# seletor.net
KiCad netlist of a schematic drawn in EAGLE
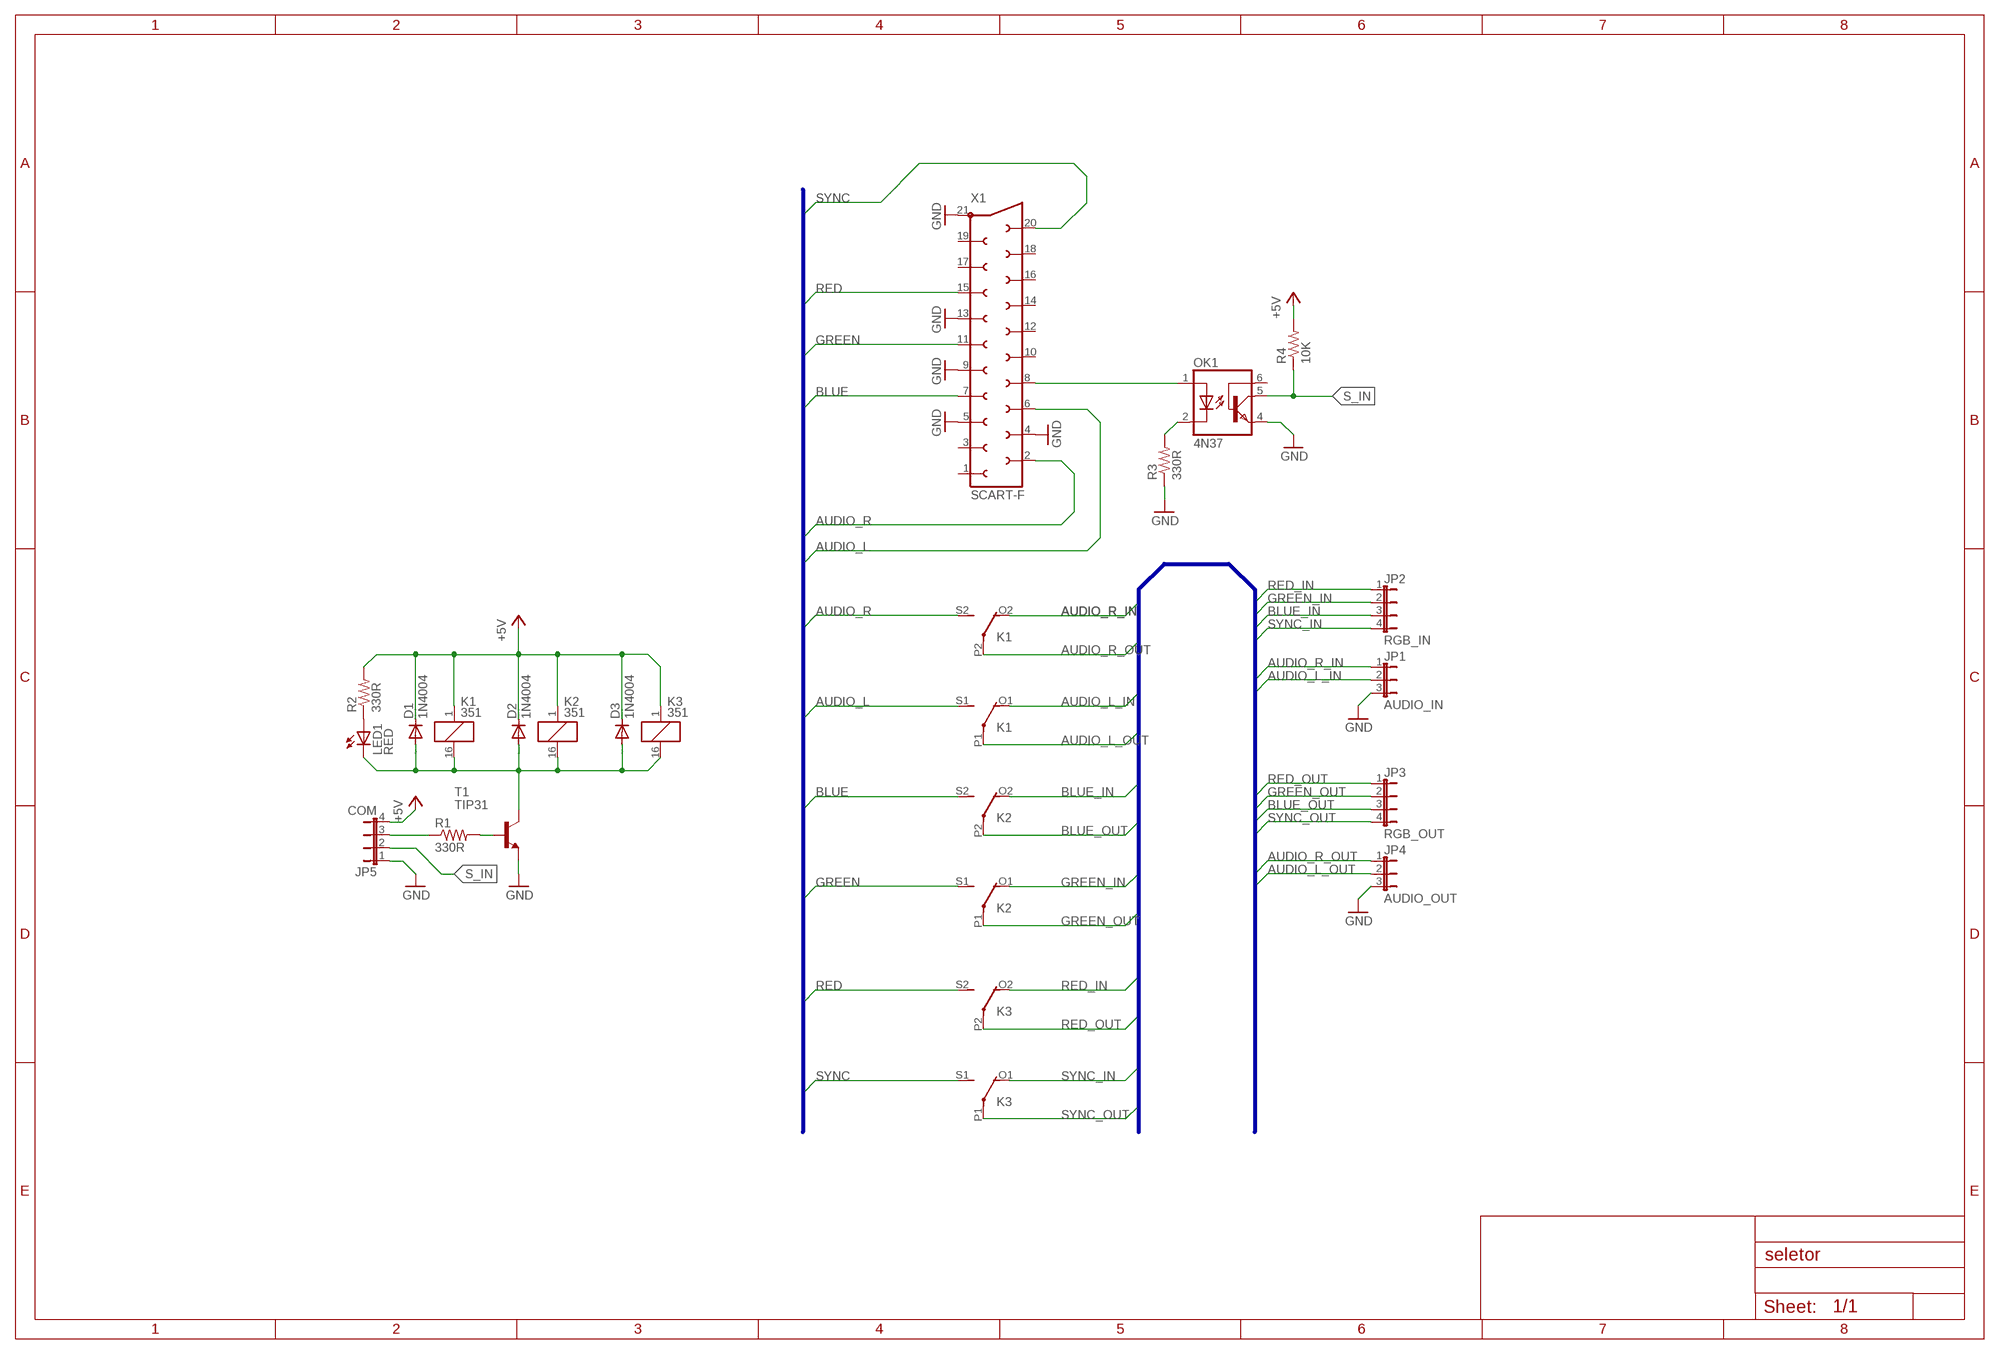
[diagram p0: schematic, sheet 1]

(export (version "E")
  (design (tool "Eeschema 10.0.6"))
  (components
    (comp (ref "D1")
      (value "1N4004")
      (footprint "eagle-import:DO41-10")
      (libsource (lib "eagle-import") (part "1N4004"))
    )
    (comp (ref "D2")
      (value "1N4004")
      (footprint "eagle-import:DO41-10")
      (libsource (lib "eagle-import") (part "1N4004"))
    )
    (comp (ref "D3")
      (value "1N4004")
      (footprint "eagle-import:DO41-10")
      (libsource (lib "eagle-import") (part "1N4004"))
    )
    (comp (ref "JP1")
      (value "AUDIO_IN")
      (footprint "eagle-import:JP2")
      (libsource (lib "eagle-import") (part "JP2E"))
    )
    (comp (ref "JP2")
      (value "RGB_IN")
      (footprint "eagle-import:JP4")
      (libsource (lib "eagle-import") (part "JP4E"))
    )
    (comp (ref "JP3")
      (value "RGB_OUT")
      (footprint "eagle-import:JP4")
      (libsource (lib "eagle-import") (part "JP4E"))
    )
    (comp (ref "JP4")
      (value "AUDIO_OUT")
      (footprint "eagle-import:JP2")
      (libsource (lib "eagle-import") (part "JP2E"))
    )
    (comp (ref "JP5")
      (value "COM")
      (footprint "eagle-import:JP4")
      (libsource (lib "eagle-import") (part "JP4E"))
    )
    (comp (ref "K1")
      (value "351")
      (footprint "eagle-import:351")
      (libsource (lib "eagle-import") (part "351"))
    )
    (comp (ref "K2")
      (value "351")
      (footprint "eagle-import:351")
      (libsource (lib "eagle-import") (part "351"))
    )
    (comp (ref "K3")
      (value "351")
      (footprint "eagle-import:351")
      (libsource (lib "eagle-import") (part "351"))
    )
    (comp (ref "LED1")
      (value "RED")
      (footprint "eagle-import:LED5MM")
      (libsource (lib "eagle-import") (part "LED5MM"))
    )
    (comp (ref "OK1")
      (value "4N37")
      (footprint "eagle-import:DIL06")
      (fields (field (name "MF") "FAIRCHILD SEMICONDUCTOR"))
      (libsource (lib "eagle-import") (part "4N37"))
    )
    (comp (ref "R1")
      (value "330R")
      (footprint "eagle-import:0204_7")
      (libsource (lib "eagle-import") (part "R-US_0204/7"))
    )
    (comp (ref "R2")
      (value "330R")
      (footprint "eagle-import:0204V")
      (libsource (lib "eagle-import") (part "R-US_0204/2V"))
    )
    (comp (ref "R3")
      (value "330R")
      (footprint "eagle-import:0204V")
      (libsource (lib "eagle-import") (part "R-US_0204/2V"))
    )
    (comp (ref "R4")
      (value "10K")
      (footprint "eagle-import:0204V")
      (libsource (lib "eagle-import") (part "R-US_0204/2V"))
    )
    (comp (ref "T1")
      (value "TIP31")
      (footprint "eagle-import:TO220")
      (libsource (lib "eagle-import") (part "TIP31"))
    )
    (comp (ref "X1")
      (value "SCART-F")
      (footprint "eagle-import:SCART-F")
      (libsource (lib "eagle-import") (part "SCART-F"))
    )
  )
  (nets
    (net (code "1") (name "+5V") (class "Default")
      (node (ref "D1") (pin "C") (pinfunction "C_C") (pintype "passive"))
      (node (ref "D2") (pin "C") (pinfunction "C_C") (pintype "passive"))
      (node (ref "D3") (pin "C") (pinfunction "C_C") (pintype "passive"))
      (node (ref "JP5") (pin "4") (pinfunction "4_4") (pintype "passive"))
      (node (ref "K1") (pin "1") (pinfunction "1_1") (pintype "passive"))
      (node (ref "K2") (pin "1") (pinfunction "1_1") (pintype "passive"))
      (node (ref "K3") (pin "1") (pinfunction "1_1") (pintype "passive"))
      (node (ref "R2") (pin "2") (pinfunction "2_2") (pintype "passive"))
      (node (ref "R4") (pin "2") (pinfunction "2_2") (pintype "passive"))
    )
    (net (code "2") (name "/AUDIO_L") (class "Default")
      (node (ref "K1") (pin "S1") (pinfunction "S_S1") (pintype "passive"))
      (node (ref "X1") (pin "6") (pinfunction "6_6") (pintype "passive"))
    )
    (net (code "3") (name "/AUDIO_L_IN") (class "Default")
      (node (ref "JP1") (pin "2") (pinfunction "2_2") (pintype "passive"))
      (node (ref "K1") (pin "O1") (pinfunction "O_O1") (pintype "passive"))
    )
    (net (code "4") (name "/AUDIO_L_OUT") (class "Default")
      (node (ref "JP4") (pin "2") (pinfunction "2_2") (pintype "passive"))
      (node (ref "K1") (pin "P1") (pinfunction "P_P1") (pintype "passive"))
    )
    (net (code "5") (name "/AUDIO_R") (class "Default")
      (node (ref "K1") (pin "S2") (pinfunction "S_S2") (pintype "passive"))
      (node (ref "X1") (pin "2") (pinfunction "2_2") (pintype "passive"))
    )
    (net (code "6") (name "/AUDIO_R_IN") (class "Default")
      (node (ref "JP1") (pin "1") (pinfunction "1_1") (pintype "passive"))
      (node (ref "K1") (pin "O2") (pinfunction "O_O2") (pintype "passive"))
    )
    (net (code "7") (name "/AUDIO_R_OUT") (class "Default")
      (node (ref "JP4") (pin "1") (pinfunction "1_1") (pintype "passive"))
      (node (ref "K1") (pin "P2") (pinfunction "P_P2") (pintype "passive"))
    )
    (net (code "8") (name "/BLUE") (class "Default")
      (node (ref "K2") (pin "S2") (pinfunction "S_S2") (pintype "passive"))
      (node (ref "X1") (pin "7") (pinfunction "7_7") (pintype "passive"))
    )
    (net (code "9") (name "/BLUE_IN") (class "Default")
      (node (ref "JP2") (pin "3") (pinfunction "3_3") (pintype "passive"))
      (node (ref "K2") (pin "O2") (pinfunction "O_O2") (pintype "passive"))
    )
    (net (code "10") (name "/BLUE_OUT") (class "Default")
      (node (ref "JP3") (pin "3") (pinfunction "3_3") (pintype "passive"))
      (node (ref "K2") (pin "P2") (pinfunction "P_P2") (pintype "passive"))
    )
    (net (code "11") (name "/GREEN") (class "Default")
      (node (ref "K2") (pin "S1") (pinfunction "S_S1") (pintype "passive"))
      (node (ref "X1") (pin "11") (pinfunction "11_11") (pintype "passive"))
    )
    (net (code "12") (name "/GREEN_IN") (class "Default")
      (node (ref "JP2") (pin "2") (pinfunction "2_2") (pintype "passive"))
      (node (ref "K2") (pin "O1") (pinfunction "O_O1") (pintype "passive"))
    )
    (net (code "13") (name "/GREEN_OUT") (class "Default")
      (node (ref "JP3") (pin "2") (pinfunction "2_2") (pintype "passive"))
      (node (ref "K2") (pin "P1") (pinfunction "P_P1") (pintype "passive"))
    )
    (net (code "14") (name "/RED") (class "Default")
      (node (ref "K3") (pin "S2") (pinfunction "S_S2") (pintype "passive"))
      (node (ref "X1") (pin "15") (pinfunction "15_15") (pintype "passive"))
    )
    (net (code "15") (name "/RED_IN") (class "Default")
      (node (ref "JP2") (pin "1") (pinfunction "1_1") (pintype "passive"))
      (node (ref "K3") (pin "O2") (pinfunction "O_O2") (pintype "passive"))
    )
    (net (code "16") (name "/RED_OUT") (class "Default")
      (node (ref "JP3") (pin "1") (pinfunction "1_1") (pintype "passive"))
      (node (ref "K3") (pin "P2") (pinfunction "P_P2") (pintype "passive"))
    )
    (net (code "17") (name "/SYNC") (class "Default")
      (node (ref "K3") (pin "S1") (pinfunction "S_S1") (pintype "passive"))
      (node (ref "X1") (pin "20") (pinfunction "20_20") (pintype "passive"))
    )
    (net (code "18") (name "/SYNC_IN") (class "Default")
      (node (ref "JP2") (pin "4") (pinfunction "4_4") (pintype "passive"))
      (node (ref "K3") (pin "O1") (pinfunction "O_O1") (pintype "passive"))
    )
    (net (code "19") (name "/SYNC_OUT") (class "Default")
      (node (ref "JP3") (pin "4") (pinfunction "4_4") (pintype "passive"))
      (node (ref "K3") (pin "P1") (pinfunction "P_P1") (pintype "passive"))
    )
    (net (code "20") (name "GND") (class "Default")
      (node (ref "JP1") (pin "3") (pinfunction "3_3") (pintype "passive"))
      (node (ref "JP4") (pin "3") (pinfunction "3_3") (pintype "passive"))
      (node (ref "JP5") (pin "1") (pinfunction "1_1") (pintype "passive"))
      (node (ref "OK1") (pin "4") (pinfunction "EMI_4") (pintype "passive"))
      (node (ref "R3") (pin "1") (pinfunction "1_1") (pintype "passive"))
      (node (ref "T1") (pin "3") (pinfunction "E_3") (pintype "passive"))
      (node (ref "X1") (pin "13") (pinfunction "13_13") (pintype "passive"))
      (node (ref "X1") (pin "21") (pinfunction "21_21") (pintype "passive"))
      (node (ref "X1") (pin "4") (pinfunction "4_4") (pintype "passive"))
      (node (ref "X1") (pin "5") (pinfunction "5_5") (pintype "passive"))
      (node (ref "X1") (pin "9") (pinfunction "9_9") (pintype "passive"))
    )
    (net (code "21") (name "Net-(JP5-Pad3)") (class "Default")
      (node (ref "JP5") (pin "3") (pinfunction "3_3") (pintype "passive"))
      (node (ref "R1") (pin "1") (pinfunction "1_1") (pintype "passive"))
    )
    (net (code "22") (name "Net-(K1A-2)") (class "Default")
      (node (ref "D1") (pin "A") (pinfunction "A_A") (pintype "passive"))
      (node (ref "D2") (pin "A") (pinfunction "A_A") (pintype "passive"))
      (node (ref "D3") (pin "A") (pinfunction "A_A") (pintype "passive"))
      (node (ref "K1") (pin "16") (pinfunction "2_16") (pintype "passive"))
      (node (ref "K2") (pin "16") (pinfunction "2_16") (pintype "passive"))
      (node (ref "K3") (pin "16") (pinfunction "2_16") (pintype "passive"))
      (node (ref "LED1") (pin "K") (pinfunction "C_K") (pintype "passive"))
      (node (ref "T1") (pin "2") (pinfunction "C_2") (pintype "passive"))
    )
    (net (code "23") (name "Net-(LED1-PadA)") (class "Default")
      (node (ref "LED1") (pin "A") (pinfunction "A_A") (pintype "passive"))
      (node (ref "R2") (pin "1") (pinfunction "1_1") (pintype "passive"))
    )
    (net (code "24") (name "Net-(OK1-A)") (class "Default")
      (node (ref "OK1") (pin "1") (pinfunction "A_1") (pintype "passive"))
      (node (ref "X1") (pin "8") (pinfunction "8_8") (pintype "passive"))
    )
    (net (code "25") (name "Net-(OK1-C)") (class "Default")
      (node (ref "OK1") (pin "2") (pinfunction "C_2") (pintype "passive"))
      (node (ref "R3") (pin "2") (pinfunction "2_2") (pintype "passive"))
    )
    (net (code "26") (name "Net-(T1-B)") (class "Default")
      (node (ref "R1") (pin "2") (pinfunction "2_2") (pintype "passive"))
      (node (ref "T1") (pin "1") (pinfunction "B_1") (pintype "passive"))
    )
    (net (code "27") (name "S_IN") (class "Default")
      (node (ref "JP5") (pin "2") (pinfunction "2_2") (pintype "passive"))
      (node (ref "OK1") (pin "5") (pinfunction "COL_5") (pintype "passive"))
      (node (ref "R4") (pin "1") (pinfunction "1_1") (pintype "passive"))
    )
    (net (code "28") (name "unconnected-(OK1-BAS-Pad6)") (class "Default")
      (node (ref "OK1") (pin "6") (pinfunction "BAS_6") (pintype "passive"))
    )
    (net (code "29") (name "unconnected-(X1-Pad1)") (class "Default")
      (node (ref "X1") (pin "1") (pinfunction "1_1") (pintype "passive"))
    )
    (net (code "30") (name "unconnected-(X1-Pad3)") (class "Default")
      (node (ref "X1") (pin "3") (pinfunction "3_3") (pintype "passive"))
    )
    (net (code "31") (name "unconnected-(X1-Pad10)") (class "Default")
      (node (ref "X1") (pin "10") (pinfunction "10_10") (pintype "passive"))
    )
    (net (code "32") (name "unconnected-(X1-Pad12)") (class "Default")
      (node (ref "X1") (pin "12") (pinfunction "12_12") (pintype "passive"))
    )
    (net (code "33") (name "unconnected-(X1-Pad14)") (class "Default")
      (node (ref "X1") (pin "14") (pinfunction "14_14") (pintype "passive"))
    )
    (net (code "34") (name "unconnected-(X1-Pad16)") (class "Default")
      (node (ref "X1") (pin "16") (pinfunction "16_16") (pintype "passive"))
    )
    (net (code "35") (name "unconnected-(X1-Pad17)") (class "Default")
      (node (ref "X1") (pin "17") (pinfunction "17_17") (pintype "passive"))
    )
    (net (code "36") (name "unconnected-(X1-Pad18)") (class "Default")
      (node (ref "X1") (pin "18") (pinfunction "18_18") (pintype "passive"))
    )
    (net (code "37") (name "unconnected-(X1-Pad19)") (class "Default")
      (node (ref "X1") (pin "19") (pinfunction "19_19") (pintype "passive"))
    )
  )
)
